# EEM_Connectors.net
KiCad netlist of a schematic drawn in Altium Designer
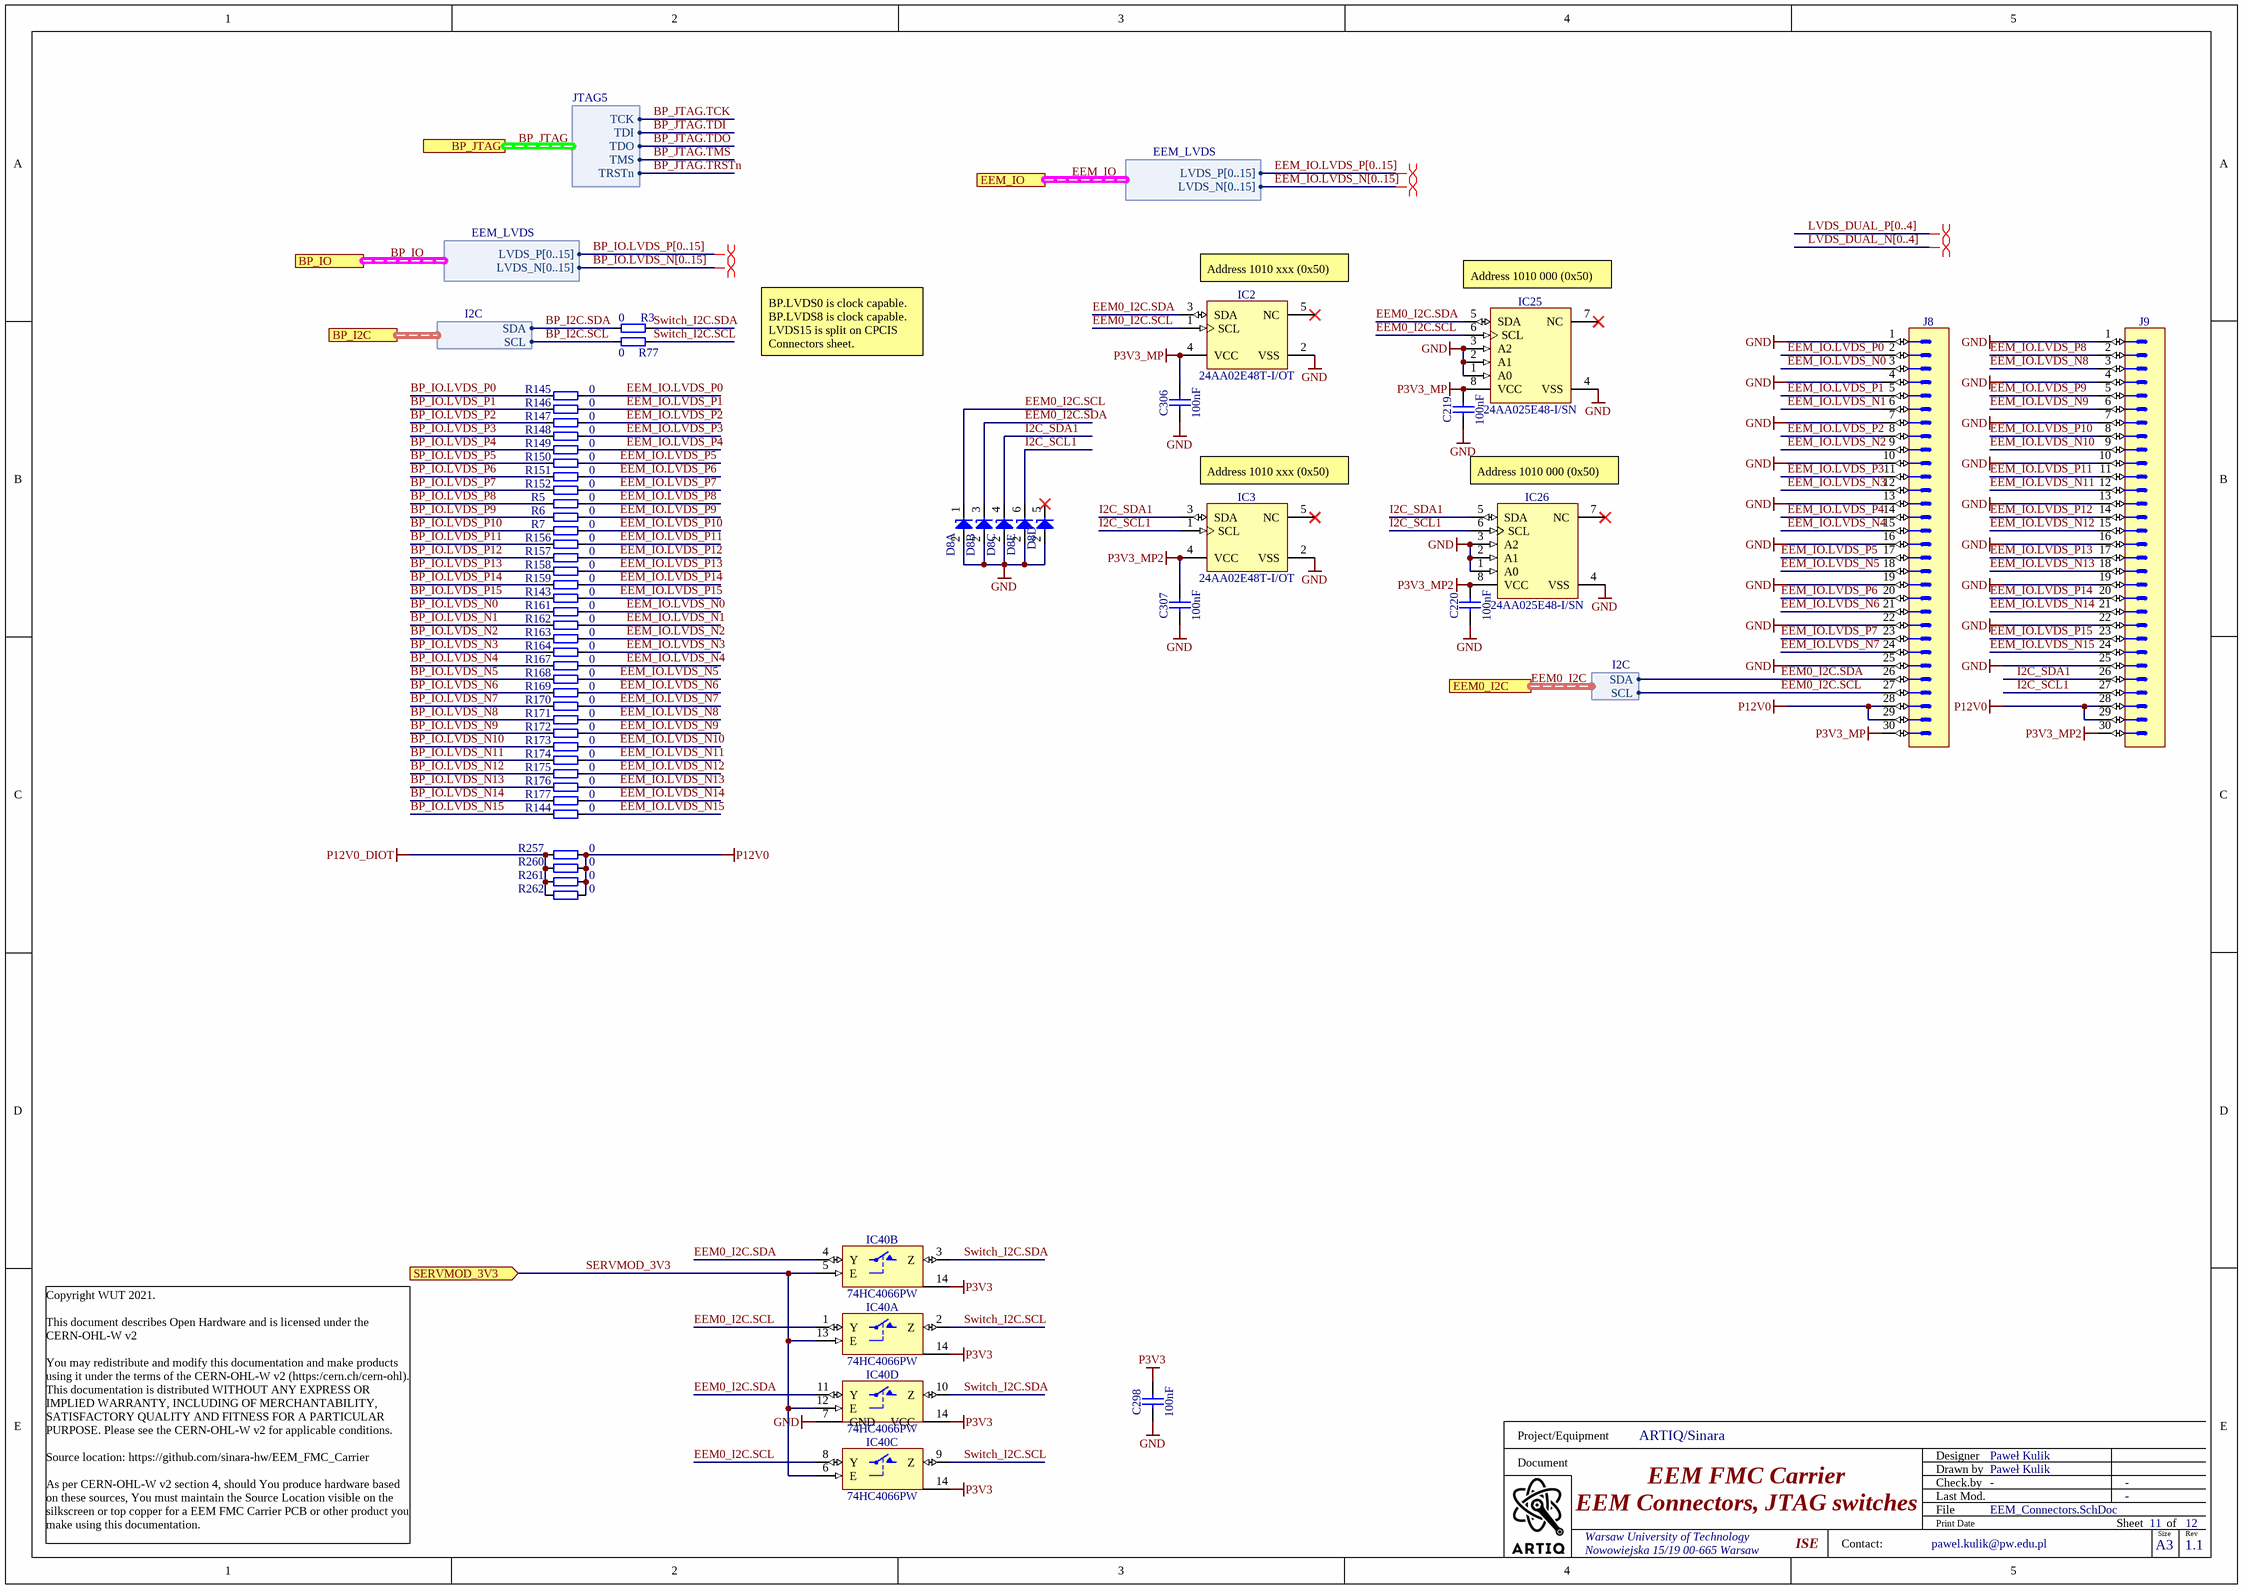
[diagram p0: EEM_Connectors.SchDoc]

(export (version "E")
  (design (tool "Eeschema 10.0.6"))
  (components
    (comp (ref "C219")
      (value "100nF")
      (footprint "CAPC1005X55N")
      (description "Non-polarised capacitor")
      (fields
        (field (name "PART NUMBER") "CC0402_100NF_25V_10%_X7R_YUDEN_TMK105B7104KVHF")
        (field (name "VOLTAGE") "25V")
        (field (name "AUTHOR") "CERN DEM JLC")
      )
      (libsource (lib "Capacitors") (part "Capacitor - non polarized"))
    )
    (comp (ref "C220")
      (value "100nF")
      (footprint "CAPC1005X55N")
      (description "Non-polarised capacitor")
      (fields
        (field (name "PART NUMBER") "CC0402_100NF_16V_10%_X5R")
        (field (name "VOLTAGE") "16V")
        (field (name "AUTHOR") "CERN DEM JLC")
      )
      (libsource (lib "Capacitors") (part "Capacitor - non polarized"))
    )
    (comp (ref "C298")
      (value "100nF")
      (footprint "CAPC1005X55N")
      (description "Non-polarised capacitor")
      (fields
        (field (name "PART NUMBER") "CC0402_100NF_16V_10%_X5R")
        (field (name "VOLTAGE") "16V")
        (field (name "AUTHOR") "CERN DEM JLC")
      )
      (libsource (lib "Capacitors") (part "Capacitor - non polarized"))
    )
    (comp (ref "C306")
      (value "100nF")
      (footprint "CAPC1005X55N")
      (description "Non-polarised capacitor")
      (fields
        (field (name "PART NUMBER") "CC0402_100NF_25V_10%_X7R_YUDEN_TMK105B7104KVHF")
        (field (name "VOLTAGE") "25V")
        (field (name "AUTHOR") "CERN DEM JLC")
      )
      (libsource (lib "Capacitors") (part "Capacitor - non polarized"))
    )
    (comp (ref "C307")
      (value "100nF")
      (footprint "CAPC1005X55N")
      (description "Non-polarised capacitor")
      (fields
        (field (name "PART NUMBER") "CC0402_100NF_25V_10%_X7R_YUDEN_TMK105B7104KVHF")
        (field (name "VOLTAGE") "25V")
        (field (name "AUTHOR") "CERN DEM JLC")
      )
      (libsource (lib "Capacitors") (part "Capacitor - non polarized"))
    )
    (comp (ref "D8")
      (value "PESD3V3L5UY")
      (footprint "SOT65P210X110-6N")
      (description "Fivefold ESD Protection Diode Arrays")
      (fields
        (field (name "VOLTAGE") "3.3V")
        (field (name "POWER") "200W")
        (field (name "AUTHOR") "CERN DEM WB")
      )
      (libsource (lib "ICs And Semiconductors") (part "PESD Array 5diodes 6pins Common anode2"))
    )
    (comp (ref "IC2")
      (value "24AA02E48T-I/OT")
      (footprint "SOT95P280X145-5N")
      (description "1.7V-5.5V, 2K I2C Serial EEPROM With EUI-48 Node Identity")
      (fields (field (name "MANUFACTURER") "MICROCHIP TECHNOLOGY") (field (name "AUTHOR") "CERN DEM MR"))
      (libsource (lib "ICs And Semiconductors") (part "24AA02E48T-I/OT"))
    )
    (comp (ref "IC3")
      (value "24AA02E48T-I/OT")
      (footprint "SOT95P280X145-5N")
      (description "1.7V-5.5V, 2K I2C Serial EEPROM With EUI-48 Node Identity")
      (fields (field (name "MANUFACTURER") "MICROCHIP TECHNOLOGY") (field (name "AUTHOR") "CERN DEM MR"))
      (libsource (lib "ICs And Semiconductors") (part "24AA02E48T-I/OT"))
    )
    (comp (ref "IC25")
      (value "24AA025E48-I/SN")
      (footprint "SOIC127P600X175-8N")
      (description "1.7V-5.5V, 2K I2C™ Serial EEPROMs with EUI-48™ Node Identity")
      (fields (field (name "MANUFACTURER") "MICROCHIP TECHNOLOGY") (field (name "AUTHOR") "CERN DEM MR"))
      (libsource (lib "ICs And Semiconductors") (part "24AA025E48-I/SN"))
    )
    (comp (ref "IC26")
      (value "24AA025E48-I/SN")
      (footprint "SOIC127P600X175-8N")
      (description "1.7V-5.5V, 2K I2C™ Serial EEPROMs with EUI-48™ Node Identity")
      (fields (field (name "MANUFACTURER") "MICROCHIP TECHNOLOGY") (field (name "AUTHOR") "CERN DEM MR"))
      (libsource (lib "ICs And Semiconductors") (part "24AA025E48-I/SN"))
    )
    (comp (ref "IC40")
      (value "74HC4066PW")
      (footprint "SOP65P640X110-14N")
      (fields (field (name "MANUFACTURER") "NXP SEMICONDUCTORS") (field (name "AUTHOR") "CERN DEM JLC"))
      (libsource (lib "ICs And Semiconductors") (part "4066"))
    )
    (comp (ref "J8")
      (value "~")
      (footprint "3M_N2530-6002RB")
      (description "Connector 30 Male")
      (fields
        (field (name "PART NUMBER") "3M_N2530-6002RB")
        (field (name "MANUFACTURER") "3M")
        (field (name "AUTHOR") "CERN DEM JLC")
      )
      (libsource (lib "Connectors") (part "Connector 30 Male"))
    )
    (comp (ref "J9")
      (value "~")
      (footprint "3M_N2530-6002RB")
      (description "Connector 30 Male")
      (fields
        (field (name "PART NUMBER") "3M_N2530-6002RB")
        (field (name "MANUFACTURER") "3M")
        (field (name "AUTHOR") "CERN DEM JLC")
      )
      (libsource (lib "Connectors") (part "Connector 30 Male"))
    )
    (comp (ref "R3")
      (value "0")
      (footprint "RESC1005X40N")
      (description "Resistor")
      (fields
        (field (name "PART NUMBER") "R0402_0R_JUMPER")
        (field (name "MANUFACTURER") "GENERIC")
        (field (name "AUTHOR") "CERN DEM JLC")
      )
      (libsource (lib "Resistors") (part "Resistor"))
    )
    (comp (ref "R5")
      (value "0")
      (footprint "RESC1005X40N")
      (description "Resistor")
      (fields
        (field (name "PART NUMBER") "R0402_0R_JUMPER")
        (field (name "MANUFACTURER") "GENERIC")
        (field (name "AUTHOR") "CERN DEM JLC")
      )
      (libsource (lib "Resistors") (part "Resistor"))
    )
    (comp (ref "R6")
      (value "0")
      (footprint "RESC1005X40N")
      (description "Resistor")
      (fields
        (field (name "PART NUMBER") "R0402_0R_JUMPER")
        (field (name "MANUFACTURER") "GENERIC")
        (field (name "AUTHOR") "CERN DEM JLC")
      )
      (libsource (lib "Resistors") (part "Resistor"))
    )
    (comp (ref "R7")
      (value "0")
      (footprint "RESC1005X40N")
      (description "Resistor")
      (fields
        (field (name "PART NUMBER") "R0402_0R_JUMPER")
        (field (name "MANUFACTURER") "GENERIC")
        (field (name "AUTHOR") "CERN DEM JLC")
      )
      (libsource (lib "Resistors") (part "Resistor"))
    )
    (comp (ref "R77")
      (value "0")
      (footprint "RESC1005X40N")
      (description "Resistor")
      (fields
        (field (name "PART NUMBER") "R0402_0R_JUMPER")
        (field (name "MANUFACTURER") "GENERIC")
        (field (name "AUTHOR") "CERN DEM JLC")
      )
      (libsource (lib "Resistors") (part "Resistor"))
    )
    (comp (ref "R143")
      (value "0")
      (footprint "RESC1005X40N")
      (description "Resistor")
      (fields
        (field (name "PART NUMBER") "R0402_0R_JUMPER")
        (field (name "MANUFACTURER") "GENERIC")
        (field (name "AUTHOR") "CERN DEM JLC")
      )
      (libsource (lib "Resistors") (part "Resistor"))
    )
    (comp (ref "R144")
      (value "0")
      (footprint "RESC1005X40N")
      (description "Resistor")
      (fields
        (field (name "PART NUMBER") "R0402_0R_JUMPER")
        (field (name "MANUFACTURER") "GENERIC")
        (field (name "AUTHOR") "CERN DEM JLC")
      )
      (libsource (lib "Resistors") (part "Resistor"))
    )
    (comp (ref "R145")
      (value "0")
      (footprint "RESC1005X40N")
      (description "Resistor")
      (fields
        (field (name "PART NUMBER") "R0402_0R_JUMPER")
        (field (name "MANUFACTURER") "GENERIC")
        (field (name "AUTHOR") "CERN DEM JLC")
      )
      (libsource (lib "Resistors") (part "Resistor"))
    )
    (comp (ref "R146")
      (value "0")
      (footprint "RESC1005X40N")
      (description "Resistor")
      (fields
        (field (name "PART NUMBER") "R0402_0R_JUMPER")
        (field (name "MANUFACTURER") "GENERIC")
        (field (name "AUTHOR") "CERN DEM JLC")
      )
      (libsource (lib "Resistors") (part "Resistor"))
    )
    (comp (ref "R147")
      (value "0")
      (footprint "RESC1005X40N")
      (description "Resistor")
      (fields
        (field (name "PART NUMBER") "R0402_0R_JUMPER")
        (field (name "MANUFACTURER") "GENERIC")
        (field (name "AUTHOR") "CERN DEM JLC")
      )
      (libsource (lib "Resistors") (part "Resistor"))
    )
    (comp (ref "R148")
      (value "0")
      (footprint "RESC1005X40N")
      (description "Resistor")
      (fields
        (field (name "PART NUMBER") "R0402_0R_JUMPER")
        (field (name "MANUFACTURER") "GENERIC")
        (field (name "AUTHOR") "CERN DEM JLC")
      )
      (libsource (lib "Resistors") (part "Resistor"))
    )
    (comp (ref "R149")
      (value "0")
      (footprint "RESC1005X40N")
      (description "Resistor")
      (fields
        (field (name "PART NUMBER") "R0402_0R_JUMPER")
        (field (name "MANUFACTURER") "GENERIC")
        (field (name "AUTHOR") "CERN DEM JLC")
      )
      (libsource (lib "Resistors") (part "Resistor"))
    )
    (comp (ref "R150")
      (value "0")
      (footprint "RESC1005X40N")
      (description "Resistor")
      (fields
        (field (name "PART NUMBER") "R0402_0R_JUMPER")
        (field (name "MANUFACTURER") "GENERIC")
        (field (name "AUTHOR") "CERN DEM JLC")
      )
      (libsource (lib "Resistors") (part "Resistor"))
    )
    (comp (ref "R151")
      (value "0")
      (footprint "RESC1005X40N")
      (description "Resistor")
      (fields
        (field (name "PART NUMBER") "R0402_0R_JUMPER")
        (field (name "MANUFACTURER") "GENERIC")
        (field (name "AUTHOR") "CERN DEM JLC")
      )
      (libsource (lib "Resistors") (part "Resistor"))
    )
    (comp (ref "R152")
      (value "0")
      (footprint "RESC1005X40N")
      (description "Resistor")
      (fields
        (field (name "PART NUMBER") "R0402_0R_JUMPER")
        (field (name "MANUFACTURER") "GENERIC")
        (field (name "AUTHOR") "CERN DEM JLC")
      )
      (libsource (lib "Resistors") (part "Resistor"))
    )
    (comp (ref "R156")
      (value "0")
      (footprint "RESC1005X40N")
      (description "Resistor")
      (fields
        (field (name "PART NUMBER") "R0402_0R_JUMPER")
        (field (name "MANUFACTURER") "GENERIC")
        (field (name "AUTHOR") "CERN DEM JLC")
      )
      (libsource (lib "Resistors") (part "Resistor"))
    )
    (comp (ref "R157")
      (value "0")
      (footprint "RESC1005X40N")
      (description "Resistor")
      (fields
        (field (name "PART NUMBER") "R0402_0R_JUMPER")
        (field (name "MANUFACTURER") "GENERIC")
        (field (name "AUTHOR") "CERN DEM JLC")
      )
      (libsource (lib "Resistors") (part "Resistor"))
    )
    (comp (ref "R158")
      (value "0")
      (footprint "RESC1005X40N")
      (description "Resistor")
      (fields
        (field (name "PART NUMBER") "R0402_0R_JUMPER")
        (field (name "MANUFACTURER") "GENERIC")
        (field (name "AUTHOR") "CERN DEM JLC")
      )
      (libsource (lib "Resistors") (part "Resistor"))
    )
    (comp (ref "R159")
      (value "0")
      (footprint "RESC1005X40N")
      (description "Resistor")
      (fields
        (field (name "PART NUMBER") "R0402_0R_JUMPER")
        (field (name "MANUFACTURER") "GENERIC")
        (field (name "AUTHOR") "CERN DEM JLC")
      )
      (libsource (lib "Resistors") (part "Resistor"))
    )
    (comp (ref "R161")
      (value "0")
      (footprint "RESC1005X40N")
      (description "Resistor")
      (fields
        (field (name "PART NUMBER") "R0402_0R_JUMPER")
        (field (name "MANUFACTURER") "GENERIC")
        (field (name "AUTHOR") "CERN DEM JLC")
      )
      (libsource (lib "Resistors") (part "Resistor"))
    )
    (comp (ref "R162")
      (value "0")
      (footprint "RESC1005X40N")
      (description "Resistor")
      (fields
        (field (name "PART NUMBER") "R0402_0R_JUMPER")
        (field (name "MANUFACTURER") "GENERIC")
        (field (name "AUTHOR") "CERN DEM JLC")
      )
      (libsource (lib "Resistors") (part "Resistor"))
    )
    (comp (ref "R163")
      (value "0")
      (footprint "RESC1005X40N")
      (description "Resistor")
      (fields
        (field (name "PART NUMBER") "R0402_0R_JUMPER")
        (field (name "MANUFACTURER") "GENERIC")
        (field (name "AUTHOR") "CERN DEM JLC")
      )
      (libsource (lib "Resistors") (part "Resistor"))
    )
    (comp (ref "R164")
      (value "0")
      (footprint "RESC1005X40N")
      (description "Resistor")
      (fields
        (field (name "PART NUMBER") "R0402_0R_JUMPER")
        (field (name "MANUFACTURER") "GENERIC")
        (field (name "AUTHOR") "CERN DEM JLC")
      )
      (libsource (lib "Resistors") (part "Resistor"))
    )
    (comp (ref "R167")
      (value "0")
      (footprint "RESC1005X40N")
      (description "Resistor")
      (fields
        (field (name "PART NUMBER") "R0402_0R_JUMPER")
        (field (name "MANUFACTURER") "GENERIC")
        (field (name "AUTHOR") "CERN DEM JLC")
      )
      (libsource (lib "Resistors") (part "Resistor"))
    )
    (comp (ref "R168")
      (value "0")
      (footprint "RESC1005X40N")
      (description "Resistor")
      (fields
        (field (name "PART NUMBER") "R0402_0R_JUMPER")
        (field (name "MANUFACTURER") "GENERIC")
        (field (name "AUTHOR") "CERN DEM JLC")
      )
      (libsource (lib "Resistors") (part "Resistor"))
    )
    (comp (ref "R169")
      (value "0")
      (footprint "RESC1005X40N")
      (description "Resistor")
      (fields
        (field (name "PART NUMBER") "R0402_0R_JUMPER")
        (field (name "MANUFACTURER") "GENERIC")
        (field (name "AUTHOR") "CERN DEM JLC")
      )
      (libsource (lib "Resistors") (part "Resistor"))
    )
    (comp (ref "R170")
      (value "0")
      (footprint "RESC1005X40N")
      (description "Resistor")
      (fields
        (field (name "PART NUMBER") "R0402_0R_JUMPER")
        (field (name "MANUFACTURER") "GENERIC")
        (field (name "AUTHOR") "CERN DEM JLC")
      )
      (libsource (lib "Resistors") (part "Resistor"))
    )
    (comp (ref "R171")
      (value "0")
      (footprint "RESC1005X40N")
      (description "Resistor")
      (fields
        (field (name "PART NUMBER") "R0402_0R_JUMPER")
        (field (name "MANUFACTURER") "GENERIC")
        (field (name "AUTHOR") "CERN DEM JLC")
      )
      (libsource (lib "Resistors") (part "Resistor"))
    )
    (comp (ref "R172")
      (value "0")
      (footprint "RESC1005X40N")
      (description "Resistor")
      (fields
        (field (name "PART NUMBER") "R0402_0R_JUMPER")
        (field (name "MANUFACTURER") "GENERIC")
        (field (name "AUTHOR") "CERN DEM JLC")
      )
      (libsource (lib "Resistors") (part "Resistor"))
    )
    (comp (ref "R173")
      (value "0")
      (footprint "RESC1005X40N")
      (description "Resistor")
      (fields
        (field (name "PART NUMBER") "R0402_0R_JUMPER")
        (field (name "MANUFACTURER") "GENERIC")
        (field (name "AUTHOR") "CERN DEM JLC")
      )
      (libsource (lib "Resistors") (part "Resistor"))
    )
    (comp (ref "R174")
      (value "0")
      (footprint "RESC1005X40N")
      (description "Resistor")
      (fields
        (field (name "PART NUMBER") "R0402_0R_JUMPER")
        (field (name "MANUFACTURER") "GENERIC")
        (field (name "AUTHOR") "CERN DEM JLC")
      )
      (libsource (lib "Resistors") (part "Resistor"))
    )
    (comp (ref "R175")
      (value "0")
      (footprint "RESC1005X40N")
      (description "Resistor")
      (fields
        (field (name "PART NUMBER") "R0402_0R_JUMPER")
        (field (name "MANUFACTURER") "GENERIC")
        (field (name "AUTHOR") "CERN DEM JLC")
      )
      (libsource (lib "Resistors") (part "Resistor"))
    )
    (comp (ref "R176")
      (value "0")
      (footprint "RESC1005X40N")
      (description "Resistor")
      (fields
        (field (name "PART NUMBER") "R0402_0R_JUMPER")
        (field (name "MANUFACTURER") "GENERIC")
        (field (name "AUTHOR") "CERN DEM JLC")
      )
      (libsource (lib "Resistors") (part "Resistor"))
    )
    (comp (ref "R177")
      (value "0")
      (footprint "RESC1005X40N")
      (description "Resistor")
      (fields
        (field (name "PART NUMBER") "R0402_0R_JUMPER")
        (field (name "MANUFACTURER") "GENERIC")
        (field (name "AUTHOR") "CERN DEM JLC")
      )
      (libsource (lib "Resistors") (part "Resistor"))
    )
    (comp (ref "R257")
      (value "0")
      (footprint "RESC1005X40N")
      (description "Resistor")
      (fields
        (field (name "PART NUMBER") "R0402_0R_JUMPER")
        (field (name "MANUFACTURER") "GENERIC")
        (field (name "AUTHOR") "CERN DEM JLC")
      )
      (libsource (lib "Resistors") (part "Resistor"))
    )
    (comp (ref "R260")
      (value "0")
      (footprint "RESC1005X40N")
      (description "Resistor")
      (fields
        (field (name "PART NUMBER") "R0402_0R_JUMPER")
        (field (name "MANUFACTURER") "GENERIC")
        (field (name "AUTHOR") "CERN DEM JLC")
      )
      (libsource (lib "Resistors") (part "Resistor"))
    )
    (comp (ref "R261")
      (value "0")
      (footprint "RESC1005X40N")
      (description "Resistor")
      (fields
        (field (name "PART NUMBER") "R0402_0R_JUMPER")
        (field (name "MANUFACTURER") "GENERIC")
        (field (name "AUTHOR") "CERN DEM JLC")
      )
      (libsource (lib "Resistors") (part "Resistor"))
    )
    (comp (ref "R262")
      (value "0")
      (footprint "RESC1005X40N")
      (description "Resistor")
      (fields
        (field (name "PART NUMBER") "R0402_0R_JUMPER")
        (field (name "MANUFACTURER") "GENERIC")
        (field (name "AUTHOR") "CERN DEM JLC")
      )
      (libsource (lib "Resistors") (part "Resistor"))
    )
  )
  (nets
    (net (code "16") (name "/BP_I2C.SCL") (class "Default")
      (node (ref "R77") (pin "1") (pinfunction "1_1") (pintype "passive"))
    )
    (net (code "17") (name "/BP_I2C.SDA") (class "Default")
      (node (ref "R3") (pin "1") (pinfunction "1_1") (pintype "passive"))
    )
    (net (code "18") (name "/BP_IO.LVDS_N0") (class "Default")
      (node (ref "R161") (pin "1") (pinfunction "1_1") (pintype "passive"))
    )
    (net (code "19") (name "/BP_IO.LVDS_N1") (class "Default")
      (node (ref "R162") (pin "1") (pinfunction "1_1") (pintype "passive"))
    )
    (net (code "20") (name "/BP_IO.LVDS_N2") (class "Default")
      (node (ref "R163") (pin "1") (pinfunction "1_1") (pintype "passive"))
    )
    (net (code "21") (name "/BP_IO.LVDS_N3") (class "Default")
      (node (ref "R164") (pin "1") (pinfunction "1_1") (pintype "passive"))
    )
    (net (code "22") (name "/BP_IO.LVDS_N4") (class "Default")
      (node (ref "R167") (pin "1") (pinfunction "1_1") (pintype "passive"))
    )
    (net (code "23") (name "/BP_IO.LVDS_N5") (class "Default")
      (node (ref "R168") (pin "1") (pinfunction "1_1") (pintype "passive"))
    )
    (net (code "24") (name "/BP_IO.LVDS_N6") (class "Default")
      (node (ref "R169") (pin "1") (pinfunction "1_1") (pintype "passive"))
    )
    (net (code "25") (name "/BP_IO.LVDS_N7") (class "Default")
      (node (ref "R170") (pin "1") (pinfunction "1_1") (pintype "passive"))
    )
    (net (code "26") (name "/BP_IO.LVDS_N8") (class "Default")
      (node (ref "R171") (pin "1") (pinfunction "1_1") (pintype "passive"))
    )
    (net (code "27") (name "/BP_IO.LVDS_N9") (class "Default")
      (node (ref "R172") (pin "1") (pinfunction "1_1") (pintype "passive"))
    )
    (net (code "28") (name "/BP_IO.LVDS_N10") (class "Default")
      (node (ref "R173") (pin "1") (pinfunction "1_1") (pintype "passive"))
    )
    (net (code "29") (name "/BP_IO.LVDS_N11") (class "Default")
      (node (ref "R174") (pin "1") (pinfunction "1_1") (pintype "passive"))
    )
    (net (code "30") (name "/BP_IO.LVDS_N12") (class "Default")
      (node (ref "R175") (pin "1") (pinfunction "1_1") (pintype "passive"))
    )
    (net (code "31") (name "/BP_IO.LVDS_N13") (class "Default")
      (node (ref "R176") (pin "1") (pinfunction "1_1") (pintype "passive"))
    )
    (net (code "32") (name "/BP_IO.LVDS_N14") (class "Default")
      (node (ref "R177") (pin "1") (pinfunction "1_1") (pintype "passive"))
    )
    (net (code "33") (name "/BP_IO.LVDS_N15") (class "Default")
      (node (ref "R144") (pin "2") (pinfunction "2_2") (pintype "passive"))
    )
    (net (code "35") (name "/BP_IO.LVDS_P0") (class "Default")
      (node (ref "R145") (pin "1") (pinfunction "1_1") (pintype "passive"))
    )
    (net (code "36") (name "/BP_IO.LVDS_P1") (class "Default")
      (node (ref "R146") (pin "1") (pinfunction "1_1") (pintype "passive"))
    )
    (net (code "37") (name "/BP_IO.LVDS_P2") (class "Default")
      (node (ref "R147") (pin "1") (pinfunction "1_1") (pintype "passive"))
    )
    (net (code "38") (name "/BP_IO.LVDS_P3") (class "Default")
      (node (ref "R148") (pin "1") (pinfunction "1_1") (pintype "passive"))
    )
    (net (code "39") (name "/BP_IO.LVDS_P4") (class "Default")
      (node (ref "R149") (pin "1") (pinfunction "1_1") (pintype "passive"))
    )
    (net (code "40") (name "/BP_IO.LVDS_P5") (class "Default")
      (node (ref "R150") (pin "1") (pinfunction "1_1") (pintype "passive"))
    )
    (net (code "41") (name "/BP_IO.LVDS_P6") (class "Default")
      (node (ref "R151") (pin "1") (pinfunction "1_1") (pintype "passive"))
    )
    (net (code "42") (name "/BP_IO.LVDS_P7") (class "Default")
      (node (ref "R152") (pin "1") (pinfunction "1_1") (pintype "passive"))
    )
    (net (code "43") (name "/BP_IO.LVDS_P8") (class "Default")
      (node (ref "R5") (pin "1") (pinfunction "1_1") (pintype "passive"))
    )
    (net (code "44") (name "/BP_IO.LVDS_P9") (class "Default")
      (node (ref "R6") (pin "1") (pinfunction "1_1") (pintype "passive"))
    )
    (net (code "45") (name "/BP_IO.LVDS_P10") (class "Default")
      (node (ref "R7") (pin "1") (pinfunction "1_1") (pintype "passive"))
    )
    (net (code "46") (name "/BP_IO.LVDS_P11") (class "Default")
      (node (ref "R156") (pin "1") (pinfunction "1_1") (pintype "passive"))
    )
    (net (code "47") (name "/BP_IO.LVDS_P12") (class "Default")
      (node (ref "R157") (pin "1") (pinfunction "1_1") (pintype "passive"))
    )
    (net (code "48") (name "/BP_IO.LVDS_P13") (class "Default")
      (node (ref "R158") (pin "1") (pinfunction "1_1") (pintype "passive"))
    )
    (net (code "49") (name "/BP_IO.LVDS_P14") (class "Default")
      (node (ref "R159") (pin "1") (pinfunction "1_1") (pintype "passive"))
    )
    (net (code "50") (name "/BP_IO.LVDS_P15") (class "Default")
      (node (ref "R143") (pin "2") (pinfunction "2_2") (pintype "passive"))
    )
    (net (code "59") (name "/EEM0_I2C.SCL") (class "Default")
      (node (ref "D8") (pin "1") (pinfunction "C_1") (pintype "passive"))
      (node (ref "IC2") (pin "1") (pinfunction "SCL_1") (pintype "input"))
      (node (ref "IC25") (pin "6") (pinfunction "SCL_6") (pintype "input"))
      (node (ref "IC40") (pin "1") (pinfunction "Y_1") (pintype "bidirectional"))
      (node (ref "IC40") (pin "8") (pinfunction "Y_8") (pintype "bidirectional"))
      (node (ref "J8") (pin "27") (pinfunction "27_27") (pintype "bidirectional"))
    )
    (net (code "60") (name "/EEM0_I2C.SDA") (class "Default")
      (node (ref "D8") (pin "3") (pinfunction "C_3") (pintype "passive"))
      (node (ref "IC2") (pin "3") (pinfunction "SDA_3") (pintype "bidirectional"))
      (node (ref "IC25") (pin "5") (pinfunction "SDA_5") (pintype "bidirectional"))
      (node (ref "IC40") (pin "11") (pinfunction "Y_11") (pintype "bidirectional"))
      (node (ref "IC40") (pin "4") (pinfunction "Y_4") (pintype "bidirectional"))
      (node (ref "J8") (pin "26") (pinfunction "26_26") (pintype "bidirectional"))
    )
    (net (code "62") (name "/EEM_IO.LVDS_N0") (class "Default")
      (node (ref "J8") (pin "3") (pinfunction "3_3") (pintype "bidirectional"))
      (node (ref "R161") (pin "2") (pinfunction "2_2") (pintype "passive"))
    )
    (net (code "63") (name "/EEM_IO.LVDS_N1") (class "Default")
      (node (ref "J8") (pin "6") (pinfunction "6_6") (pintype "bidirectional"))
      (node (ref "R162") (pin "2") (pinfunction "2_2") (pintype "passive"))
    )
    (net (code "64") (name "/EEM_IO.LVDS_N2") (class "Default")
      (node (ref "J8") (pin "9") (pinfunction "9_9") (pintype "bidirectional"))
      (node (ref "R163") (pin "2") (pinfunction "2_2") (pintype "passive"))
    )
    (net (code "65") (name "/EEM_IO.LVDS_N3") (class "Default")
      (node (ref "J8") (pin "12") (pinfunction "12_12") (pintype "bidirectional"))
      (node (ref "R164") (pin "2") (pinfunction "2_2") (pintype "passive"))
    )
    (net (code "66") (name "/EEM_IO.LVDS_N4") (class "Default")
      (node (ref "J8") (pin "15") (pinfunction "15_15") (pintype "bidirectional"))
      (node (ref "R167") (pin "2") (pinfunction "2_2") (pintype "passive"))
    )
    (net (code "67") (name "/EEM_IO.LVDS_N5") (class "Default")
      (node (ref "J8") (pin "18") (pinfunction "18_18") (pintype "bidirectional"))
      (node (ref "R168") (pin "2") (pinfunction "2_2") (pintype "passive"))
    )
    (net (code "68") (name "/EEM_IO.LVDS_N6") (class "Default")
      (node (ref "J8") (pin "21") (pinfunction "21_21") (pintype "bidirectional"))
      (node (ref "R169") (pin "2") (pinfunction "2_2") (pintype "passive"))
    )
    (net (code "69") (name "/EEM_IO.LVDS_N7") (class "Default")
      (node (ref "J8") (pin "24") (pinfunction "24_24") (pintype "bidirectional"))
      (node (ref "R170") (pin "2") (pinfunction "2_2") (pintype "passive"))
    )
    (net (code "70") (name "/EEM_IO.LVDS_N8") (class "Default")
      (node (ref "J9") (pin "3") (pinfunction "3_3") (pintype "bidirectional"))
      (node (ref "R171") (pin "2") (pinfunction "2_2") (pintype "passive"))
    )
    (net (code "71") (name "/EEM_IO.LVDS_N9") (class "Default")
      (node (ref "J9") (pin "6") (pinfunction "6_6") (pintype "bidirectional"))
      (node (ref "R172") (pin "2") (pinfunction "2_2") (pintype "passive"))
    )
    (net (code "72") (name "/EEM_IO.LVDS_N10") (class "Default")
      (node (ref "J9") (pin "9") (pinfunction "9_9") (pintype "bidirectional"))
      (node (ref "R173") (pin "2") (pinfunction "2_2") (pintype "passive"))
    )
    (net (code "73") (name "/EEM_IO.LVDS_N11") (class "Default")
      (node (ref "J9") (pin "12") (pinfunction "12_12") (pintype "bidirectional"))
      (node (ref "R174") (pin "2") (pinfunction "2_2") (pintype "passive"))
    )
    (net (code "74") (name "/EEM_IO.LVDS_N12") (class "Default")
      (node (ref "J9") (pin "15") (pinfunction "15_15") (pintype "bidirectional"))
      (node (ref "R175") (pin "2") (pinfunction "2_2") (pintype "passive"))
    )
    (net (code "75") (name "/EEM_IO.LVDS_N13") (class "Default")
      (node (ref "J9") (pin "18") (pinfunction "18_18") (pintype "bidirectional"))
      (node (ref "R176") (pin "2") (pinfunction "2_2") (pintype "passive"))
    )
    (net (code "76") (name "/EEM_IO.LVDS_N14") (class "Default")
      (node (ref "J9") (pin "21") (pinfunction "21_21") (pintype "bidirectional"))
      (node (ref "R177") (pin "2") (pinfunction "2_2") (pintype "passive"))
    )
    (net (code "77") (name "/EEM_IO.LVDS_N15") (class "Default")
      (node (ref "J9") (pin "24") (pinfunction "24_24") (pintype "bidirectional"))
      (node (ref "R144") (pin "1") (pinfunction "1_1") (pintype "passive"))
    )
    (net (code "79") (name "/EEM_IO.LVDS_P0") (class "Default")
      (node (ref "J8") (pin "2") (pinfunction "2_2") (pintype "bidirectional"))
      (node (ref "R145") (pin "2") (pinfunction "2_2") (pintype "passive"))
    )
    (net (code "80") (name "/EEM_IO.LVDS_P1") (class "Default")
      (node (ref "J8") (pin "5") (pinfunction "5_5") (pintype "bidirectional"))
      (node (ref "R146") (pin "2") (pinfunction "2_2") (pintype "passive"))
    )
    (net (code "81") (name "/EEM_IO.LVDS_P2") (class "Default")
      (node (ref "J8") (pin "8") (pinfunction "8_8") (pintype "bidirectional"))
      (node (ref "R147") (pin "2") (pinfunction "2_2") (pintype "passive"))
    )
    (net (code "82") (name "/EEM_IO.LVDS_P3") (class "Default")
      (node (ref "J8") (pin "11") (pinfunction "11_11") (pintype "bidirectional"))
      (node (ref "R148") (pin "2") (pinfunction "2_2") (pintype "passive"))
    )
    (net (code "83") (name "/EEM_IO.LVDS_P4") (class "Default")
      (node (ref "J8") (pin "14") (pinfunction "14_14") (pintype "bidirectional"))
      (node (ref "R149") (pin "2") (pinfunction "2_2") (pintype "passive"))
    )
    (net (code "84") (name "/EEM_IO.LVDS_P5") (class "Default")
      (node (ref "J8") (pin "17") (pinfunction "17_17") (pintype "bidirectional"))
      (node (ref "R150") (pin "2") (pinfunction "2_2") (pintype "passive"))
    )
    (net (code "85") (name "/EEM_IO.LVDS_P6") (class "Default")
      (node (ref "J8") (pin "20") (pinfunction "20_20") (pintype "bidirectional"))
      (node (ref "R151") (pin "2") (pinfunction "2_2") (pintype "passive"))
    )
    (net (code "86") (name "/EEM_IO.LVDS_P7") (class "Default")
      (node (ref "J8") (pin "23") (pinfunction "23_23") (pintype "bidirectional"))
      (node (ref "R152") (pin "2") (pinfunction "2_2") (pintype "passive"))
    )
    (net (code "87") (name "/EEM_IO.LVDS_P8") (class "Default")
      (node (ref "J9") (pin "2") (pinfunction "2_2") (pintype "bidirectional"))
      (node (ref "R5") (pin "2") (pinfunction "2_2") (pintype "passive"))
    )
    (net (code "88") (name "/EEM_IO.LVDS_P9") (class "Default")
      (node (ref "J9") (pin "5") (pinfunction "5_5") (pintype "bidirectional"))
      (node (ref "R6") (pin "2") (pinfunction "2_2") (pintype "passive"))
    )
    (net (code "89") (name "/EEM_IO.LVDS_P10") (class "Default")
      (node (ref "J9") (pin "8") (pinfunction "8_8") (pintype "bidirectional"))
      (node (ref "R7") (pin "2") (pinfunction "2_2") (pintype "passive"))
    )
    (net (code "90") (name "/EEM_IO.LVDS_P11") (class "Default")
      (node (ref "J9") (pin "11") (pinfunction "11_11") (pintype "bidirectional"))
      (node (ref "R156") (pin "2") (pinfunction "2_2") (pintype "passive"))
    )
    (net (code "91") (name "/EEM_IO.LVDS_P12") (class "Default")
      (node (ref "J9") (pin "14") (pinfunction "14_14") (pintype "bidirectional"))
      (node (ref "R157") (pin "2") (pinfunction "2_2") (pintype "passive"))
    )
    (net (code "92") (name "/EEM_IO.LVDS_P13") (class "Default")
      (node (ref "J9") (pin "17") (pinfunction "17_17") (pintype "bidirectional"))
      (node (ref "R158") (pin "2") (pinfunction "2_2") (pintype "passive"))
    )
    (net (code "93") (name "/EEM_IO.LVDS_P14") (class "Default")
      (node (ref "J9") (pin "20") (pinfunction "20_20") (pintype "bidirectional"))
      (node (ref "R159") (pin "2") (pinfunction "2_2") (pintype "passive"))
    )
    (net (code "94") (name "/EEM_IO.LVDS_P15") (class "Default")
      (node (ref "J9") (pin "23") (pinfunction "23_23") (pintype "bidirectional"))
      (node (ref "R143") (pin "1") (pinfunction "1_1") (pintype "passive"))
    )
    (net (code "95") (name "/I2C_SCL1") (class "Default")
      (node (ref "D8") (pin "6") (pinfunction "C_6") (pintype "passive"))
      (node (ref "IC26") (pin "6") (pinfunction "SCL_6") (pintype "input"))
      (node (ref "IC3") (pin "1") (pinfunction "SCL_1") (pintype "input"))
      (node (ref "J9") (pin "27") (pinfunction "27_27") (pintype "bidirectional"))
    )
    (net (code "96") (name "/I2C_SDA1") (class "Default")
      (node (ref "D8") (pin "4") (pinfunction "C_4") (pintype "passive"))
      (node (ref "IC26") (pin "5") (pinfunction "SDA_5") (pintype "bidirectional"))
      (node (ref "IC3") (pin "3") (pinfunction "SDA_3") (pintype "bidirectional"))
      (node (ref "J9") (pin "26") (pinfunction "26_26") (pintype "bidirectional"))
    )
    (net (code "99") (name "/SERVMOD_3V3") (class "Default")
      (node (ref "IC40") (pin "12") (pinfunction "E_12") (pintype "input"))
      (node (ref "IC40") (pin "13") (pinfunction "E_13") (pintype "input"))
      (node (ref "IC40") (pin "5") (pinfunction "E_5") (pintype "input"))
      (node (ref "IC40") (pin "6") (pinfunction "E_6") (pintype "input"))
    )
    (net (code "100") (name "/Switch_I2C.SCL") (class "Default")
      (node (ref "IC40") (pin "2") (pinfunction "Z_2") (pintype "bidirectional"))
      (node (ref "IC40") (pin "9") (pinfunction "Z_9") (pintype "bidirectional"))
      (node (ref "R77") (pin "2") (pinfunction "2_2") (pintype "passive"))
    )
    (net (code "101") (name "/Switch_I2C.SDA") (class "Default")
      (node (ref "IC40") (pin "10") (pinfunction "Z_10") (pintype "bidirectional"))
      (node (ref "IC40") (pin "3") (pinfunction "Z_3") (pintype "bidirectional"))
      (node (ref "R3") (pin "2") (pinfunction "2_2") (pintype "passive"))
    )
    (net (code "105") (name "GND") (class "Default")
      (node (ref "C219") (pin "1") (pinfunction "1_1") (pintype "passive"))
      (node (ref "C220") (pin "1") (pinfunction "1_1") (pintype "passive"))
      (node (ref "C298") (pin "1") (pinfunction "1_1") (pintype "passive"))
      (node (ref "C306") (pin "1") (pinfunction "1_1") (pintype "passive"))
      (node (ref "C307") (pin "1") (pinfunction "1_1") (pintype "passive"))
      (node (ref "D8") (pin "2") (pinfunction "A_2") (pintype "passive"))
      (node (ref "IC2") (pin "2") (pinfunction "VSS_2") (pintype "power_in"))
      (node (ref "IC25") (pin "1") (pinfunction "A0_1") (pintype "input"))
      (node (ref "IC25") (pin "2") (pinfunction "A1_2") (pintype "input"))
      (node (ref "IC25") (pin "3") (pinfunction "A2_3") (pintype "input"))
      (node (ref "IC25") (pin "4") (pinfunction "VSS_4") (pintype "power_in"))
      (node (ref "IC26") (pin "1") (pinfunction "A0_1") (pintype "input"))
      (node (ref "IC26") (pin "2") (pinfunction "A1_2") (pintype "input"))
      (node (ref "IC26") (pin "3") (pinfunction "A2_3") (pintype "input"))
      (node (ref "IC26") (pin "4") (pinfunction "VSS_4") (pintype "power_in"))
      (node (ref "IC3") (pin "2") (pinfunction "VSS_2") (pintype "power_in"))
      (node (ref "IC40") (pin "7") (pinfunction "GND_7") (pintype "power_in"))
      (node (ref "J8") (pin "1") (pinfunction "1_1") (pintype "bidirectional"))
      (node (ref "J8") (pin "10") (pinfunction "10_10") (pintype "bidirectional"))
      (node (ref "J8") (pin "13") (pinfunction "13_13") (pintype "bidirectional"))
      (node (ref "J8") (pin "16") (pinfunction "16_16") (pintype "bidirectional"))
      (node (ref "J8") (pin "19") (pinfunction "19_19") (pintype "bidirectional"))
      (node (ref "J8") (pin "22") (pinfunction "22_22") (pintype "bidirectional"))
      (node (ref "J8") (pin "25") (pinfunction "25_25") (pintype "bidirectional"))
      (node (ref "J8") (pin "4") (pinfunction "4_4") (pintype "bidirectional"))
      (node (ref "J8") (pin "7") (pinfunction "7_7") (pintype "bidirectional"))
      (node (ref "J9") (pin "1") (pinfunction "1_1") (pintype "bidirectional"))
      (node (ref "J9") (pin "10") (pinfunction "10_10") (pintype "bidirectional"))
      (node (ref "J9") (pin "13") (pinfunction "13_13") (pintype "bidirectional"))
      (node (ref "J9") (pin "16") (pinfunction "16_16") (pintype "bidirectional"))
      (node (ref "J9") (pin "19") (pinfunction "19_19") (pintype "bidirectional"))
      (node (ref "J9") (pin "22") (pinfunction "22_22") (pintype "bidirectional"))
      (node (ref "J9") (pin "25") (pinfunction "25_25") (pintype "bidirectional"))
      (node (ref "J9") (pin "4") (pinfunction "4_4") (pintype "bidirectional"))
      (node (ref "J9") (pin "7") (pinfunction "7_7") (pintype "bidirectional"))
    )
    (net (code "106") (name "P3V3") (class "Default")
      (node (ref "C298") (pin "2") (pinfunction "2_2") (pintype "passive"))
      (node (ref "IC40") (pin "14") (pinfunction "VCC_14") (pintype "power_in"))
    )
    (net (code "107") (name "P3V3_MP") (class "Default")
      (node (ref "C219") (pin "2") (pinfunction "2_2") (pintype "passive"))
      (node (ref "C306") (pin "2") (pinfunction "2_2") (pintype "passive"))
      (node (ref "IC2") (pin "4") (pinfunction "VCC_4") (pintype "power_in"))
      (node (ref "IC25") (pin "8") (pinfunction "VCC_8") (pintype "power_in"))
      (node (ref "J8") (pin "30") (pinfunction "30_30") (pintype "bidirectional"))
    )
    (net (code "108") (name "P3V3_MP2") (class "Default")
      (node (ref "C220") (pin "2") (pinfunction "2_2") (pintype "passive"))
      (node (ref "C307") (pin "2") (pinfunction "2_2") (pintype "passive"))
      (node (ref "IC26") (pin "8") (pinfunction "VCC_8") (pintype "power_in"))
      (node (ref "IC3") (pin "4") (pinfunction "VCC_4") (pintype "power_in"))
      (node (ref "J9") (pin "30") (pinfunction "30_30") (pintype "bidirectional"))
    )
    (net (code "109") (name "P12V0") (class "Default")
      (node (ref "J8") (pin "28") (pinfunction "28_28") (pintype "bidirectional"))
      (node (ref "J8") (pin "29") (pinfunction "29_29") (pintype "bidirectional"))
      (node (ref "J9") (pin "28") (pinfunction "28_28") (pintype "bidirectional"))
      (node (ref "J9") (pin "29") (pinfunction "29_29") (pintype "bidirectional"))
      (node (ref "R257") (pin "2") (pinfunction "2_2") (pintype "passive"))
      (node (ref "R260") (pin "2") (pinfunction "2_2") (pintype "passive"))
      (node (ref "R261") (pin "2") (pinfunction "2_2") (pintype "passive"))
      (node (ref "R262") (pin "2") (pinfunction "2_2") (pintype "passive"))
    )
    (net (code "110") (name "P12V0_DIOT") (class "Default")
      (node (ref "R257") (pin "1") (pinfunction "1_1") (pintype "passive"))
      (node (ref "R260") (pin "1") (pinfunction "1_1") (pintype "passive"))
      (node (ref "R261") (pin "1") (pinfunction "1_1") (pintype "passive"))
      (node (ref "R262") (pin "1") (pinfunction "1_1") (pintype "passive"))
    )
    (net (code "111") (name "unconnected-(D8D-C-Pad5)") (class "Default")
      (node (ref "D8") (pin "5") (pinfunction "C_5") (pintype "passive+no_connect"))
    )
    (net (code "112") (name "unconnected-(IC2-NC-Pad5)") (class "Default")
      (node (ref "IC2") (pin "5") (pinfunction "NC_5") (pintype "passive+no_connect"))
    )
    (net (code "113") (name "unconnected-(IC3-NC-Pad5)") (class "Default")
      (node (ref "IC3") (pin "5") (pinfunction "NC_5") (pintype "passive+no_connect"))
    )
    (net (code "114") (name "unconnected-(IC25-NC-Pad7)") (class "Default")
      (node (ref "IC25") (pin "7") (pinfunction "NC_7") (pintype "passive+no_connect"))
    )
    (net (code "115") (name "unconnected-(IC26-NC-Pad7)") (class "Default")
      (node (ref "IC26") (pin "7") (pinfunction "NC_7") (pintype "passive+no_connect"))
    )
  )
)
